# phy1.net
KiCad netlist of a schematic drawn in Altium Designer
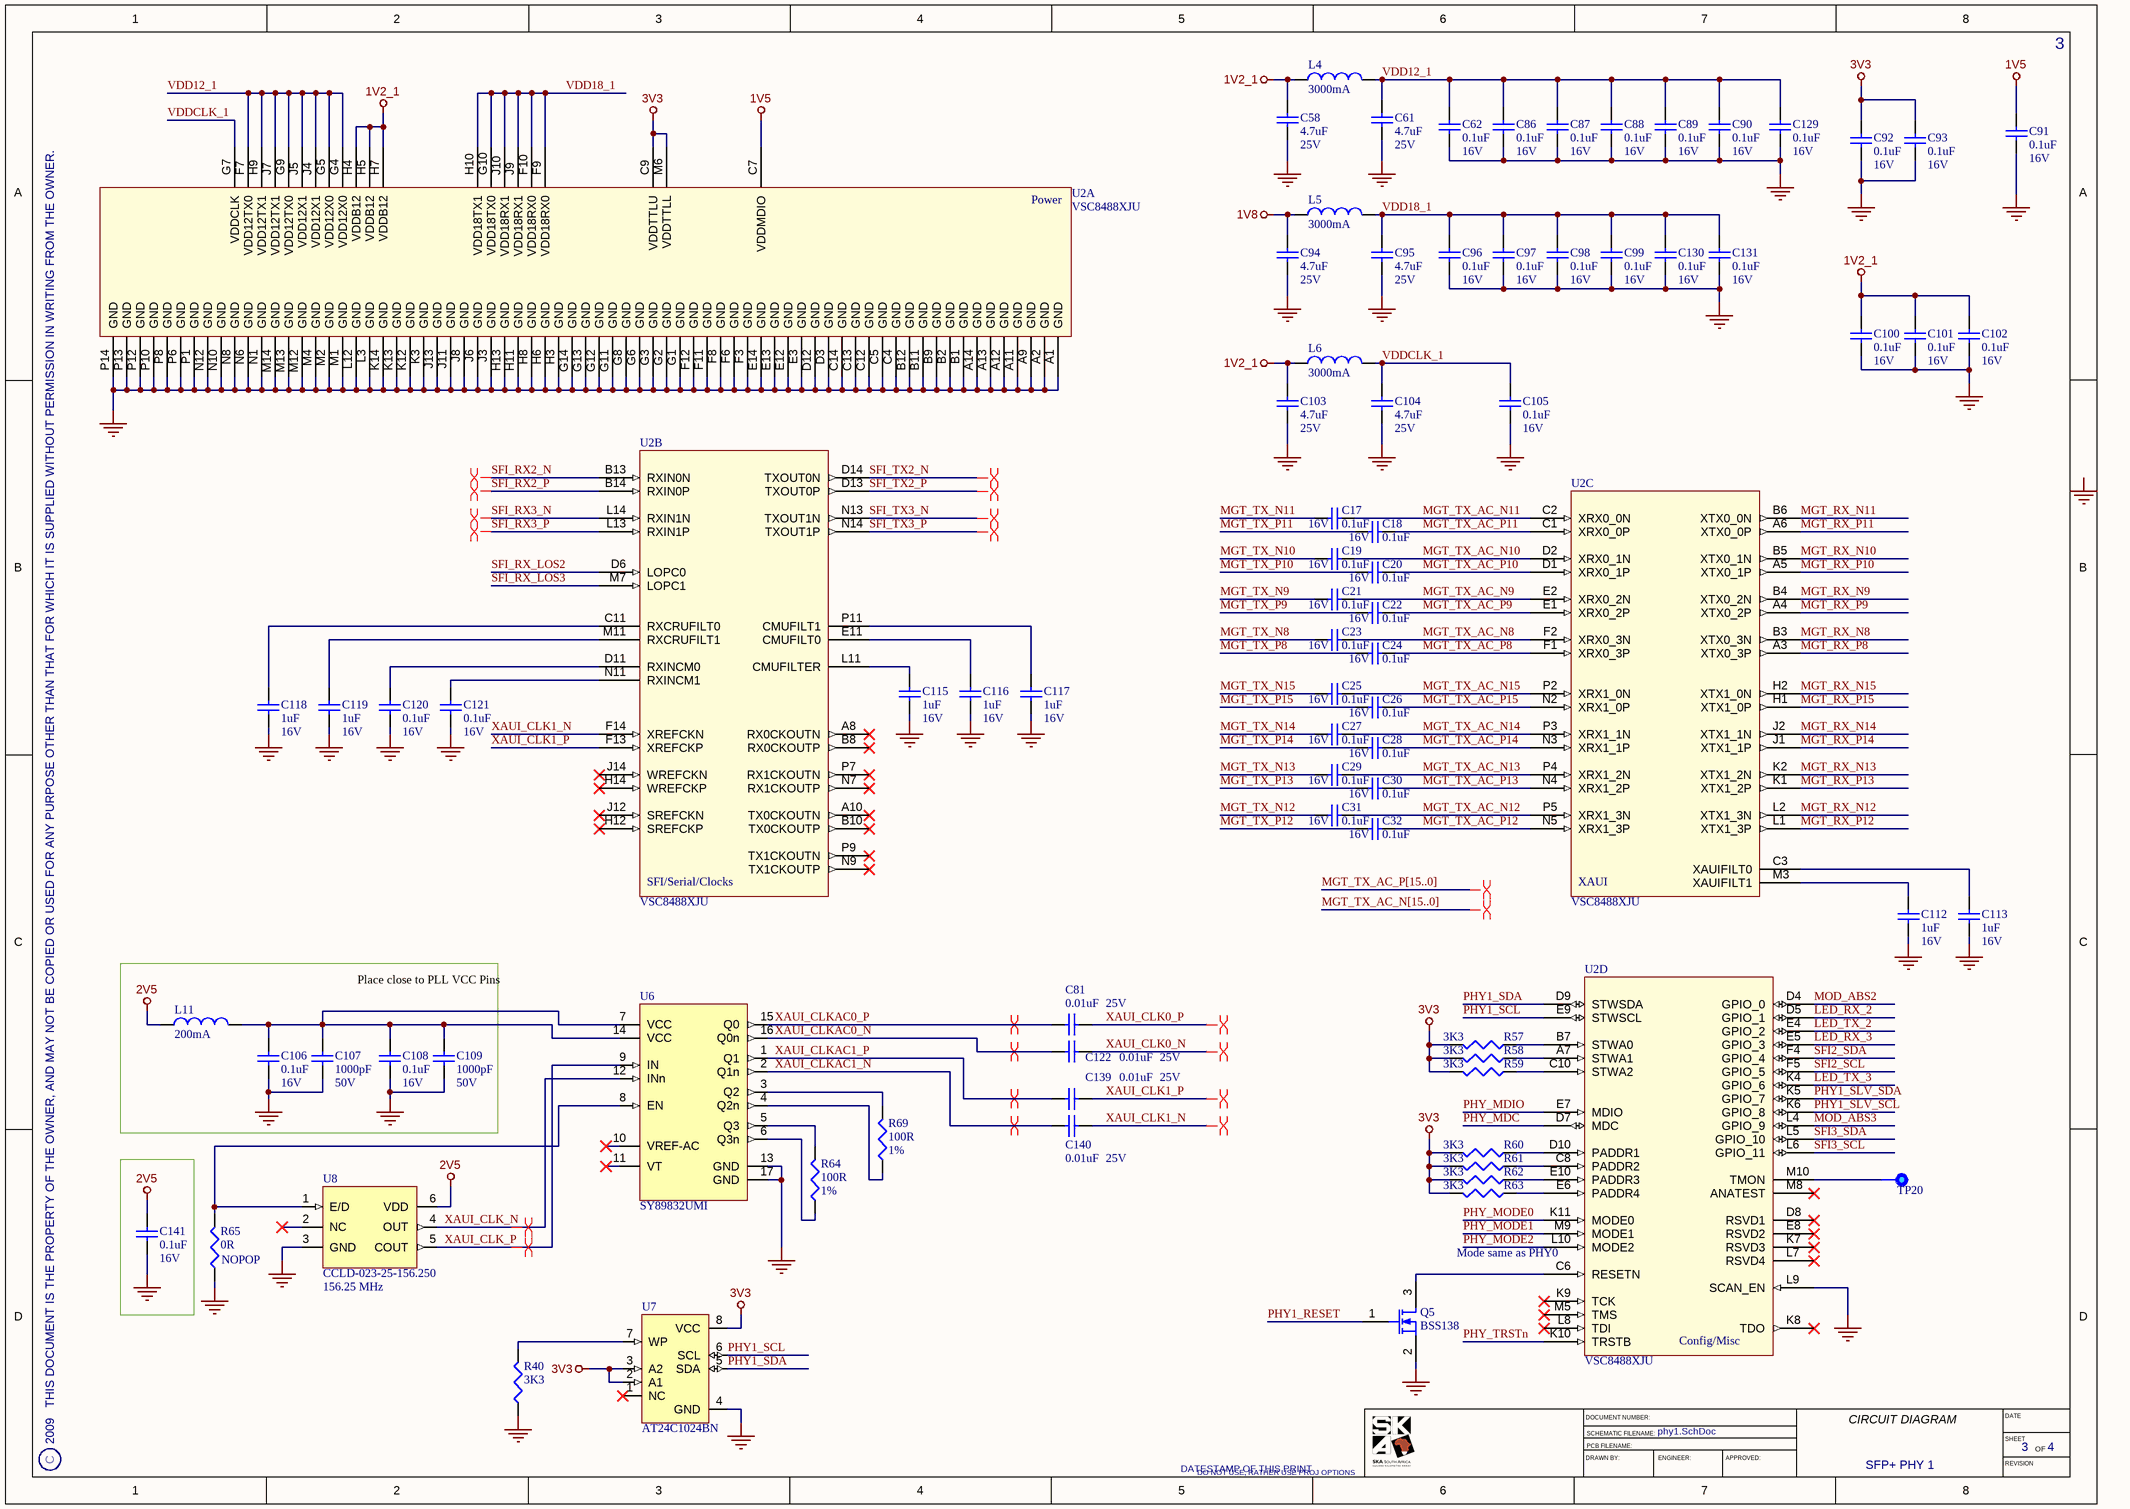
[diagram p0: phy1.SchDoc]

(export (version "E")
  (design (tool "Eeschema 10.0.6"))
  (components
    (comp (ref "C17")
      (value "0.1uF")
      (footprint "CAPC1005X60L")
      (description "0.1uF, Ceramic Capacitor")
      (fields
        (field (name "RATING") "16V")
        (field (name "MANUFACTURER") "VENKEL")
        (field (name "PARTNUM") "C0402X7R160-104KN")
      )
      (libsource (lib "altium_db") (part "CapStd"))
    )
    (comp (ref "C18")
      (value "0.1uF")
      (footprint "CAPC1005X60L")
      (description "0.1uF, Ceramic Capacitor")
      (fields
        (field (name "RATING") "16V")
        (field (name "MANUFACTURER") "VENKEL")
        (field (name "PARTNUM") "C0402X7R160-104KN")
      )
      (libsource (lib "altium_db") (part "CapStd"))
    )
    (comp (ref "C19")
      (value "0.1uF")
      (footprint "CAPC1005X60L")
      (description "0.1uF, Ceramic Capacitor")
      (fields
        (field (name "RATING") "16V")
        (field (name "MANUFACTURER") "VENKEL")
        (field (name "PARTNUM") "C0402X7R160-104KN")
      )
      (libsource (lib "altium_db") (part "CapStd"))
    )
    (comp (ref "C20")
      (value "0.1uF")
      (footprint "CAPC1005X60L")
      (description "0.1uF, Ceramic Capacitor")
      (fields
        (field (name "RATING") "16V")
        (field (name "MANUFACTURER") "VENKEL")
        (field (name "PARTNUM") "C0402X7R160-104KN")
      )
      (libsource (lib "altium_db") (part "CapStd"))
    )
    (comp (ref "C21")
      (value "0.1uF")
      (footprint "CAPC1005X60L")
      (description "0.1uF, Ceramic Capacitor")
      (fields
        (field (name "RATING") "16V")
        (field (name "MANUFACTURER") "VENKEL")
        (field (name "PARTNUM") "C0402X7R160-104KN")
      )
      (libsource (lib "altium_db") (part "CapStd"))
    )
    (comp (ref "C22")
      (value "0.1uF")
      (footprint "CAPC1005X60L")
      (description "0.1uF, Ceramic Capacitor")
      (fields
        (field (name "RATING") "16V")
        (field (name "MANUFACTURER") "VENKEL")
        (field (name "PARTNUM") "C0402X7R160-104KN")
      )
      (libsource (lib "altium_db") (part "CapStd"))
    )
    (comp (ref "C23")
      (value "0.1uF")
      (footprint "CAPC1005X60L")
      (description "0.1uF, Ceramic Capacitor")
      (fields
        (field (name "RATING") "16V")
        (field (name "MANUFACTURER") "VENKEL")
        (field (name "PARTNUM") "C0402X7R160-104KN")
      )
      (libsource (lib "altium_db") (part "CapStd"))
    )
    (comp (ref "C24")
      (value "0.1uF")
      (footprint "CAPC1005X60L")
      (description "0.1uF, Ceramic Capacitor")
      (fields
        (field (name "RATING") "16V")
        (field (name "MANUFACTURER") "VENKEL")
        (field (name "PARTNUM") "C0402X7R160-104KN")
      )
      (libsource (lib "altium_db") (part "CapStd"))
    )
    (comp (ref "C25")
      (value "0.1uF")
      (footprint "CAPC1005X60L")
      (description "0.1uF, Ceramic Capacitor")
      (fields
        (field (name "RATING") "16V")
        (field (name "MANUFACTURER") "VENKEL")
        (field (name "PARTNUM") "C0402X7R160-104KN")
      )
      (libsource (lib "altium_db") (part "CapStd"))
    )
    (comp (ref "C26")
      (value "0.1uF")
      (footprint "CAPC1005X60L")
      (description "0.1uF, Ceramic Capacitor")
      (fields
        (field (name "RATING") "16V")
        (field (name "MANUFACTURER") "VENKEL")
        (field (name "PARTNUM") "C0402X7R160-104KN")
      )
      (libsource (lib "altium_db") (part "CapStd"))
    )
    (comp (ref "C27")
      (value "0.1uF")
      (footprint "CAPC1005X60L")
      (description "0.1uF, Ceramic Capacitor")
      (fields
        (field (name "RATING") "16V")
        (field (name "MANUFACTURER") "VENKEL")
        (field (name "PARTNUM") "C0402X7R160-104KN")
      )
      (libsource (lib "altium_db") (part "CapStd"))
    )
    (comp (ref "C28")
      (value "0.1uF")
      (footprint "CAPC1005X60L")
      (description "0.1uF, Ceramic Capacitor")
      (fields
        (field (name "RATING") "16V")
        (field (name "MANUFACTURER") "VENKEL")
        (field (name "PARTNUM") "C0402X7R160-104KN")
      )
      (libsource (lib "altium_db") (part "CapStd"))
    )
    (comp (ref "C29")
      (value "0.1uF")
      (footprint "CAPC1005X60L")
      (description "0.1uF, Ceramic Capacitor")
      (fields
        (field (name "RATING") "16V")
        (field (name "MANUFACTURER") "VENKEL")
        (field (name "PARTNUM") "C0402X7R160-104KN")
      )
      (libsource (lib "altium_db") (part "CapStd"))
    )
    (comp (ref "C30")
      (value "0.1uF")
      (footprint "CAPC1005X60L")
      (description "0.1uF, Ceramic Capacitor")
      (fields
        (field (name "RATING") "16V")
        (field (name "MANUFACTURER") "VENKEL")
        (field (name "PARTNUM") "C0402X7R160-104KN")
      )
      (libsource (lib "altium_db") (part "CapStd"))
    )
    (comp (ref "C31")
      (value "0.1uF")
      (footprint "CAPC1005X60L")
      (description "0.1uF, Ceramic Capacitor")
      (fields
        (field (name "RATING") "16V")
        (field (name "MANUFACTURER") "VENKEL")
        (field (name "PARTNUM") "C0402X7R160-104KN")
      )
      (libsource (lib "altium_db") (part "CapStd"))
    )
    (comp (ref "C32")
      (value "0.1uF")
      (footprint "CAPC1005X60L")
      (description "0.1uF, Ceramic Capacitor")
      (fields
        (field (name "RATING") "16V")
        (field (name "MANUFACTURER") "VENKEL")
        (field (name "PARTNUM") "C0402X7R160-104KN")
      )
      (libsource (lib "altium_db") (part "CapStd"))
    )
    (comp (ref "C58")
      (value "4.7uF")
      (footprint "CAPC2012X127L")
      (description "4.7uF, Ceramic Capacitor")
      (fields
        (field (name "RATING") "25V")
        (field (name "MANUFACTURER") "MURATA")
        (field (name "PARTNUM") "GRM21BR61E475KA12K")
      )
      (libsource (lib "altium_db") (part "CapStd"))
    )
    (comp (ref "C61")
      (value "4.7uF")
      (footprint "CAPC2012X127L")
      (description "4.7uF, Ceramic Capacitor")
      (fields
        (field (name "RATING") "25V")
        (field (name "MANUFACTURER") "MURATA")
        (field (name "PARTNUM") "GRM21BR61E475KA12K")
      )
      (libsource (lib "altium_db") (part "CapStd"))
    )
    (comp (ref "C62")
      (value "0.1uF")
      (footprint "CAPC1005X60L")
      (description "0.1uF, Ceramic Capacitor")
      (fields
        (field (name "RATING") "16V")
        (field (name "MANUFACTURER") "VENKEL")
        (field (name "PARTNUM") "C0402X7R160-104KN")
      )
      (libsource (lib "altium_db") (part "CapStd"))
    )
    (comp (ref "C81")
      (value "0.01uF")
      (footprint "CAPC1005X55L")
      (description "0.01uF, Ceramic Capacitor")
      (fields
        (field (name "RATING") "25V")
        (field (name "MANUFACTURER") "MURATA")
        (field (name "PARTNUM") "GRM155R71E103KA01D")
      )
      (libsource (lib "altium_db") (part "CapStd"))
    )
    (comp (ref "C86")
      (value "0.1uF")
      (footprint "CAPC1005X60L")
      (description "0.1uF, Ceramic Capacitor")
      (fields
        (field (name "RATING") "16V")
        (field (name "MANUFACTURER") "VENKEL")
        (field (name "PARTNUM") "C0402X7R160-104KN")
      )
      (libsource (lib "altium_db") (part "CapStd"))
    )
    (comp (ref "C87")
      (value "0.1uF")
      (footprint "CAPC1005X60L")
      (description "0.1uF, Ceramic Capacitor")
      (fields
        (field (name "RATING") "16V")
        (field (name "MANUFACTURER") "VENKEL")
        (field (name "PARTNUM") "C0402X7R160-104KN")
      )
      (libsource (lib "altium_db") (part "CapStd"))
    )
    (comp (ref "C88")
      (value "0.1uF")
      (footprint "CAPC1005X60L")
      (description "0.1uF, Ceramic Capacitor")
      (fields
        (field (name "RATING") "16V")
        (field (name "MANUFACTURER") "VENKEL")
        (field (name "PARTNUM") "C0402X7R160-104KN")
      )
      (libsource (lib "altium_db") (part "CapStd"))
    )
    (comp (ref "C89")
      (value "0.1uF")
      (footprint "CAPC1005X60L")
      (description "0.1uF, Ceramic Capacitor")
      (fields
        (field (name "RATING") "16V")
        (field (name "MANUFACTURER") "VENKEL")
        (field (name "PARTNUM") "C0402X7R160-104KN")
      )
      (libsource (lib "altium_db") (part "CapStd"))
    )
    (comp (ref "C90")
      (value "0.1uF")
      (footprint "CAPC1005X60L")
      (description "0.1uF, Ceramic Capacitor")
      (fields
        (field (name "RATING") "16V")
        (field (name "MANUFACTURER") "VENKEL")
        (field (name "PARTNUM") "C0402X7R160-104KN")
      )
      (libsource (lib "altium_db") (part "CapStd"))
    )
    (comp (ref "C91")
      (value "0.1uF")
      (footprint "CAPC1005X60L")
      (description "0.1uF, Ceramic Capacitor")
      (fields
        (field (name "RATING") "16V")
        (field (name "MANUFACTURER") "VENKEL")
        (field (name "PARTNUM") "C0402X7R160-104KN")
      )
      (libsource (lib "altium_db") (part "CapStd"))
    )
    (comp (ref "C92")
      (value "0.1uF")
      (footprint "CAPC1005X60L")
      (description "0.1uF, Ceramic Capacitor")
      (fields
        (field (name "RATING") "16V")
        (field (name "MANUFACTURER") "VENKEL")
        (field (name "PARTNUM") "C0402X7R160-104KN")
      )
      (libsource (lib "altium_db") (part "CapStd"))
    )
    (comp (ref "C93")
      (value "0.1uF")
      (footprint "CAPC1005X60L")
      (description "0.1uF, Ceramic Capacitor")
      (fields
        (field (name "RATING") "16V")
        (field (name "MANUFACTURER") "VENKEL")
        (field (name "PARTNUM") "C0402X7R160-104KN")
      )
      (libsource (lib "altium_db") (part "CapStd"))
    )
    (comp (ref "C94")
      (value "4.7uF")
      (footprint "CAPC2012X127L")
      (description "4.7uF, Ceramic Capacitor")
      (fields
        (field (name "RATING") "25V")
        (field (name "MANUFACTURER") "MURATA")
        (field (name "PARTNUM") "GRM21BR61E475KA12K")
      )
      (libsource (lib "altium_db") (part "CapStd"))
    )
    (comp (ref "C95")
      (value "4.7uF")
      (footprint "CAPC2012X127L")
      (description "4.7uF, Ceramic Capacitor")
      (fields
        (field (name "RATING") "25V")
        (field (name "MANUFACTURER") "MURATA")
        (field (name "PARTNUM") "GRM21BR61E475KA12K")
      )
      (libsource (lib "altium_db") (part "CapStd"))
    )
    (comp (ref "C96")
      (value "0.1uF")
      (footprint "CAPC1005X60L")
      (description "0.1uF, Ceramic Capacitor")
      (fields
        (field (name "RATING") "16V")
        (field (name "MANUFACTURER") "VENKEL")
        (field (name "PARTNUM") "C0402X7R160-104KN")
      )
      (libsource (lib "altium_db") (part "CapStd"))
    )
    (comp (ref "C97")
      (value "0.1uF")
      (footprint "CAPC1005X60L")
      (description "0.1uF, Ceramic Capacitor")
      (fields
        (field (name "RATING") "16V")
        (field (name "MANUFACTURER") "VENKEL")
        (field (name "PARTNUM") "C0402X7R160-104KN")
      )
      (libsource (lib "altium_db") (part "CapStd"))
    )
    (comp (ref "C98")
      (value "0.1uF")
      (footprint "CAPC1005X60L")
      (description "0.1uF, Ceramic Capacitor")
      (fields
        (field (name "RATING") "16V")
        (field (name "MANUFACTURER") "VENKEL")
        (field (name "PARTNUM") "C0402X7R160-104KN")
      )
      (libsource (lib "altium_db") (part "CapStd"))
    )
    (comp (ref "C99")
      (value "0.1uF")
      (footprint "CAPC1005X60L")
      (description "0.1uF, Ceramic Capacitor")
      (fields
        (field (name "RATING") "16V")
        (field (name "MANUFACTURER") "VENKEL")
        (field (name "PARTNUM") "C0402X7R160-104KN")
      )
      (libsource (lib "altium_db") (part "CapStd"))
    )
    (comp (ref "C100")
      (value "0.1uF")
      (footprint "CAPC1005X60L")
      (description "0.1uF, Ceramic Capacitor")
      (fields
        (field (name "RATING") "16V")
        (field (name "MANUFACTURER") "VENKEL")
        (field (name "PARTNUM") "C0402X7R160-104KN")
      )
      (libsource (lib "altium_db") (part "CapStd"))
    )
    (comp (ref "C101")
      (value "0.1uF")
      (footprint "CAPC1005X60L")
      (description "0.1uF, Ceramic Capacitor")
      (fields
        (field (name "RATING") "16V")
        (field (name "MANUFACTURER") "VENKEL")
        (field (name "PARTNUM") "C0402X7R160-104KN")
      )
      (libsource (lib "altium_db") (part "CapStd"))
    )
    (comp (ref "C102")
      (value "0.1uF")
      (footprint "CAPC1005X60L")
      (description "0.1uF, Ceramic Capacitor")
      (fields
        (field (name "RATING") "16V")
        (field (name "MANUFACTURER") "VENKEL")
        (field (name "PARTNUM") "C0402X7R160-104KN")
      )
      (libsource (lib "altium_db") (part "CapStd"))
    )
    (comp (ref "C103")
      (value "4.7uF")
      (footprint "CAPC2012X127L")
      (description "4.7uF, Ceramic Capacitor")
      (fields
        (field (name "RATING") "25V")
        (field (name "MANUFACTURER") "MURATA")
        (field (name "PARTNUM") "GRM21BR61E475KA12K")
      )
      (libsource (lib "altium_db") (part "CapStd"))
    )
    (comp (ref "C104")
      (value "4.7uF")
      (footprint "CAPC2012X127L")
      (description "4.7uF, Ceramic Capacitor")
      (fields
        (field (name "RATING") "25V")
        (field (name "MANUFACTURER") "MURATA")
        (field (name "PARTNUM") "GRM21BR61E475KA12K")
      )
      (libsource (lib "altium_db") (part "CapStd"))
    )
    (comp (ref "C105")
      (value "0.1uF")
      (footprint "CAPC1005X60L")
      (description "0.1uF, Ceramic Capacitor")
      (fields
        (field (name "RATING") "16V")
        (field (name "MANUFACTURER") "VENKEL")
        (field (name "PARTNUM") "C0402X7R160-104KN")
      )
      (libsource (lib "altium_db") (part "CapStd"))
    )
    (comp (ref "C106")
      (value "0.1uF")
      (footprint "CAPC1005X60L")
      (description "0.1uF, Ceramic Capacitor")
      (fields
        (field (name "RATING") "16V")
        (field (name "MANUFACTURER") "VENKEL")
        (field (name "PARTNUM") "C0402X7R160-104KN")
      )
      (libsource (lib "altium_db") (part "CapStd"))
    )
    (comp (ref "C107")
      (value "1000pF")
      (footprint "CAPC1005X55L")
      (description "1000pF, Ceramic Capacitor")
      (fields
        (field (name "RATING") "50V")
        (field (name "MANUFACTURER") "MURATA")
        (field (name "PARTNUM") "GRM155R61H102KA01D")
      )
      (libsource (lib "altium_db") (part "CapStd"))
    )
    (comp (ref "C108")
      (value "0.1uF")
      (footprint "CAPC1005X60L")
      (description "0.1uF, Ceramic Capacitor")
      (fields
        (field (name "RATING") "16V")
        (field (name "MANUFACTURER") "VENKEL")
        (field (name "PARTNUM") "C0402X7R160-104KN")
      )
      (libsource (lib "altium_db") (part "CapStd"))
    )
    (comp (ref "C109")
      (value "1000pF")
      (footprint "CAPC1005X55L")
      (description "1000pF, Ceramic Capacitor")
      (fields
        (field (name "RATING") "50V")
        (field (name "MANUFACTURER") "MURATA")
        (field (name "PARTNUM") "GRM155R61H102KA01D")
      )
      (libsource (lib "altium_db") (part "CapStd"))
    )
    (comp (ref "C112")
      (value "1uF")
      (footprint "CAPC2012X127L")
      (description "1uF, Ceramic Capacitor")
      (fields
        (field (name "RATING") "16V")
        (field (name "MANUFACTURER") "MURATA")
        (field (name "PARTNUM") "GRM21BR61C105KA01L")
      )
      (libsource (lib "altium_db") (part "CapStd"))
    )
    (comp (ref "C113")
      (value "1uF")
      (footprint "CAPC2012X127L")
      (description "1uF, Ceramic Capacitor")
      (fields
        (field (name "RATING") "16V")
        (field (name "MANUFACTURER") "MURATA")
        (field (name "PARTNUM") "GRM21BR61C105KA01L")
      )
      (libsource (lib "altium_db") (part "CapStd"))
    )
    (comp (ref "C115")
      (value "1uF")
      (footprint "CAPC2012X127L")
      (description "1uF, Ceramic Capacitor")
      (fields
        (field (name "RATING") "16V")
        (field (name "MANUFACTURER") "MURATA")
        (field (name "PARTNUM") "GRM21BR61C105KA01L")
      )
      (libsource (lib "altium_db") (part "CapStd"))
    )
    (comp (ref "C116")
      (value "1uF")
      (footprint "CAPC2012X127L")
      (description "1uF, Ceramic Capacitor")
      (fields
        (field (name "RATING") "16V")
        (field (name "MANUFACTURER") "MURATA")
        (field (name "PARTNUM") "GRM21BR61C105KA01L")
      )
      (libsource (lib "altium_db") (part "CapStd"))
    )
    (comp (ref "C117")
      (value "1uF")
      (footprint "CAPC2012X127L")
      (description "1uF, Ceramic Capacitor")
      (fields
        (field (name "RATING") "16V")
        (field (name "MANUFACTURER") "MURATA")
        (field (name "PARTNUM") "GRM21BR61C105KA01L")
      )
      (libsource (lib "altium_db") (part "CapStd"))
    )
    (comp (ref "C118")
      (value "1uF")
      (footprint "CAPC2012X127L")
      (description "1uF, Ceramic Capacitor")
      (fields
        (field (name "RATING") "16V")
        (field (name "MANUFACTURER") "MURATA")
        (field (name "PARTNUM") "GRM21BR61C105KA01L")
      )
      (libsource (lib "altium_db") (part "CapStd"))
    )
    (comp (ref "C119")
      (value "1uF")
      (footprint "CAPC2012X127L")
      (description "1uF, Ceramic Capacitor")
      (fields
        (field (name "RATING") "16V")
        (field (name "MANUFACTURER") "MURATA")
        (field (name "PARTNUM") "GRM21BR61C105KA01L")
      )
      (libsource (lib "altium_db") (part "CapStd"))
    )
    (comp (ref "C120")
      (value "0.1uF")
      (footprint "CAPC1005X60L")
      (description "0.1uF, Ceramic Capacitor")
      (fields
        (field (name "RATING") "16V")
        (field (name "MANUFACTURER") "VENKEL")
        (field (name "PARTNUM") "C0402X7R160-104KN")
      )
      (libsource (lib "altium_db") (part "CapStd"))
    )
    (comp (ref "C121")
      (value "0.1uF")
      (footprint "CAPC1005X60L")
      (description "0.1uF, Ceramic Capacitor")
      (fields
        (field (name "RATING") "16V")
        (field (name "MANUFACTURER") "VENKEL")
        (field (name "PARTNUM") "C0402X7R160-104KN")
      )
      (libsource (lib "altium_db") (part "CapStd"))
    )
    (comp (ref "C122")
      (value "0.01uF")
      (footprint "CAPC1005X55L")
      (description "0.01uF, Ceramic Capacitor")
      (fields
        (field (name "RATING") "25V")
        (field (name "MANUFACTURER") "MURATA")
        (field (name "PARTNUM") "GRM155R71E103KA01D")
      )
      (libsource (lib "altium_db") (part "CapStd"))
    )
    (comp (ref "C129")
      (value "0.1uF")
      (footprint "CAPC1005X60L")
      (description "0.1uF, Ceramic Capacitor")
      (fields
        (field (name "RATING") "16V")
        (field (name "MANUFACTURER") "VENKEL")
        (field (name "PARTNUM") "C0402X7R160-104KN")
      )
      (libsource (lib "altium_db") (part "CapStd"))
    )
    (comp (ref "C130")
      (value "0.1uF")
      (footprint "CAPC1005X60L")
      (description "0.1uF, Ceramic Capacitor")
      (fields
        (field (name "RATING") "16V")
        (field (name "MANUFACTURER") "VENKEL")
        (field (name "PARTNUM") "C0402X7R160-104KN")
      )
      (libsource (lib "altium_db") (part "CapStd"))
    )
    (comp (ref "C131")
      (value "0.1uF")
      (footprint "CAPC1005X60L")
      (description "0.1uF, Ceramic Capacitor")
      (fields
        (field (name "RATING") "16V")
        (field (name "MANUFACTURER") "VENKEL")
        (field (name "PARTNUM") "C0402X7R160-104KN")
      )
      (libsource (lib "altium_db") (part "CapStd"))
    )
    (comp (ref "C139")
      (value "0.01uF")
      (footprint "CAPC1005X55L")
      (description "0.01uF, Ceramic Capacitor")
      (fields
        (field (name "RATING") "25V")
        (field (name "MANUFACTURER") "MURATA")
        (field (name "PARTNUM") "GRM155R71E103KA01D")
      )
      (libsource (lib "altium_db") (part "CapStd"))
    )
    (comp (ref "C140")
      (value "0.01uF")
      (footprint "CAPC1005X55L")
      (description "0.01uF, Ceramic Capacitor")
      (fields
        (field (name "RATING") "25V")
        (field (name "MANUFACTURER") "MURATA")
        (field (name "PARTNUM") "GRM155R71E103KA01D")
      )
      (libsource (lib "altium_db") (part "CapStd"))
    )
    (comp (ref "C141")
      (value "0.1uF")
      (footprint "CAPC1005X60L")
      (description "0.1uF, Ceramic Capacitor")
      (fields
        (field (name "RATING") "16V")
        (field (name "MANUFACTURER") "VENKEL")
        (field (name "PARTNUM") "C0402X7R160-104KN")
      )
      (libsource (lib "altium_db") (part "CapStd"))
    )
    (comp (ref "L4")
      (value "120R")
      (footprint "INDC3216X130L")
      (description "120 Ohm, Chip Ferrite Brad")
      (fields
        (field (name "RATING") "3000mA")
        (field (name "MANUFACTURER") "Murata")
        (field (name "PARTNUM") "BLM31PG121SN1")
      )
      (libsource (lib "altium_db") (part "IndStd"))
    )
    (comp (ref "L5")
      (value "120R")
      (footprint "INDC3216X130L")
      (description "120 Ohm, Chip Ferrite Brad")
      (fields
        (field (name "RATING") "3000mA")
        (field (name "MANUFACTURER") "Murata")
        (field (name "PARTNUM") "BLM31PG121SN1")
      )
      (libsource (lib "altium_db") (part "IndStd"))
    )
    (comp (ref "L6")
      (value "120R")
      (footprint "INDC3216X130L")
      (description "120 Ohm, Chip Ferrite Brad")
      (fields
        (field (name "RATING") "3000mA")
        (field (name "MANUFACTURER") "Murata")
        (field (name "PARTNUM") "BLM31PG121SN1")
      )
      (libsource (lib "altium_db") (part "IndStd"))
    )
    (comp (ref "L11")
      (value "600R")
      (footprint "INDC2012X130L")
      (description "600 Ohm, Chip Ferrite Bead")
      (fields
        (field (name "RATING") "200mA")
        (field (name "MANUFACTURER") "Murata")
        (field (name "PARTNUM") "BLM21BD601SN1")
      )
      (libsource (lib "altium_db") (part "IndStd"))
    )
    (comp (ref "Q5")
      (value "BSS138")
      (footprint "SOT95P245X110-3N")
      (description "N-Channel Logic Level Enhancement Mode Field Effect Transistor")
      (fields (field (name "MANUFACTURER") "Fairchild Semiconductor"))
      (libsource (lib "altium_db") (part "BSS138"))
    )
    (comp (ref "R40")
      (value "3K3")
      (footprint "RESC1005X40L")
      (description "3K3, 1.1mm x 0.5mm, Thick Film Resistor")
      (fields (field (name "MANUFACTURER") "ROYALOHM") (field (name "PARTNUM") "0402WGJ0332T1E"))
      (libsource (lib "altium_db") (part "ResStd"))
    )
    (comp (ref "R57")
      (value "3K3")
      (footprint "RESC1005X40L")
      (description "3K3, 1.1mm x 0.5mm, Thick Film Resistor")
      (fields (field (name "MANUFACTURER") "ROYALOHM") (field (name "PARTNUM") "0402WGJ0332T1E"))
      (libsource (lib "altium_db") (part "ResStd"))
    )
    (comp (ref "R58")
      (value "3K3")
      (footprint "RESC1005X40L")
      (description "3K3, 1.1mm x 0.5mm, Thick Film Resistor")
      (fields (field (name "MANUFACTURER") "ROYALOHM") (field (name "PARTNUM") "0402WGJ0332T1E"))
      (libsource (lib "altium_db") (part "ResStd"))
    )
    (comp (ref "R59")
      (value "3K3")
      (footprint "RESC1005X40L")
      (description "3K3, 1.1mm x 0.5mm, Thick Film Resistor")
      (fields (field (name "MANUFACTURER") "ROYALOHM") (field (name "PARTNUM") "0402WGJ0332T1E"))
      (libsource (lib "altium_db") (part "ResStd"))
    )
    (comp (ref "R60")
      (value "3K3")
      (footprint "RESC1005X40L")
      (description "3K3, 1.1mm x 0.5mm, Thick Film Resistor")
      (fields (field (name "MANUFACTURER") "ROYALOHM") (field (name "PARTNUM") "0402WGJ0332T1E"))
      (libsource (lib "altium_db") (part "ResStd"))
    )
    (comp (ref "R61")
      (value "3K3")
      (footprint "RESC1005X40L")
      (description "3K3, 1.1mm x 0.5mm, Thick Film Resistor")
      (fields (field (name "MANUFACTURER") "ROYALOHM") (field (name "PARTNUM") "0402WGJ0332T1E"))
      (libsource (lib "altium_db") (part "ResStd"))
    )
    (comp (ref "R62")
      (value "3K3")
      (footprint "RESC1005X40L")
      (description "3K3, 1.1mm x 0.5mm, Thick Film Resistor")
      (fields (field (name "MANUFACTURER") "ROYALOHM") (field (name "PARTNUM") "0402WGJ0332T1E"))
      (libsource (lib "altium_db") (part "ResStd"))
    )
    (comp (ref "R63")
      (value "3K3")
      (footprint "RESC1005X40L")
      (description "3K3, 1.1mm x 0.5mm, Thick Film Resistor")
      (fields (field (name "MANUFACTURER") "ROYALOHM") (field (name "PARTNUM") "0402WGJ0332T1E"))
      (libsource (lib "altium_db") (part "ResStd"))
    )
    (comp (ref "R64")
      (value "100R")
      (footprint "RESC1005X40L")
      (description "100R, 1.1mm x 0.5mm, Thick Film Resistor")
      (fields
        (field (name "MANUFACTURER") "ROYALOHM")
        (field (name "PARTNUM") "0402WGF0101T1E")
        (field (name "TOLERANCE") "1%")
      )
      (libsource (lib "altium_db") (part "ResStd"))
    )
    (comp (ref "R65")
      (value "0R")
      (footprint "RESC1005X40L")
      (description "0R, 1.1mm x 0.5mm, Thick Film Resistor")
      (fields (field (name "MANUFACTURER") "ROYALOHM") (field (name "PARTNUM") "0402WG00000T1E"))
      (libsource (lib "altium_db") (part "ResStd"))
    )
    (comp (ref "R69")
      (value "100R")
      (footprint "RESC1005X40L")
      (description "100R, 1.1mm x 0.5mm, Thick Film Resistor")
      (fields
        (field (name "MANUFACTURER") "ROYALOHM")
        (field (name "PARTNUM") "0402WGF0101T1E")
        (field (name "TOLERANCE") "1%")
      )
      (libsource (lib "altium_db") (part "ResStd"))
    )
    (comp (ref "TP20")
      (value "Testpoint")
      (footprint "TP100")
      (description "1mm Diameter, through-hole, Circular Test-point")
      (libsource (lib "altium_db") (part "Testpoint"))
    )
    (comp (ref "U2")
      (value "VSC8488XJU")
      (footprint "BGA196C100P14X14_1500x1500x140")
      (description "DualChannel WAN/LAN/Backplane XAUI to SFP+/KR Transceiver")
      (fields (field (name "MANUFACTURER") "Vitesse"))
      (libsource (lib "altium_db") (part "VSC8488XJU"))
    )
    (comp (ref "U6")
      (value "SY89832UMI")
      (footprint "MLF-16")
      (description "2.5 C Ultra-precision 1:4 LVDS Fanout Buffer/Translator with Interal Termination")
      (fields (field (name "MANUFACTURER") "Micrel"))
      (libsource (lib "altium_db") (part "SY89832UMI"))
    )
    (comp (ref "U7")
      (value "AT24C1024BN")
      (footprint "SOIC150-8_N")
      (description "1M, SOIC-8, Serial EEPROM")
      (fields (field (name "MANUFACTURER") "Atmel") (field (name "PARTNUM") "AT24C1024BN-SH-B"))
      (libsource (lib "altium_db") (part "AT24C1024BN-SH"))
    )
    (comp (ref "U8")
      (value "CCLD-023-25-156.250")
      (footprint "CCLD-023X-XX-XXX_XXX")
      (description "156.25 MHz, Low-Jitter Differential LVDS Clock Oscillator")
      (fields
        (field (name "PARTNUM") "CCLD-023-25-156.250")
        (field (name "FREQUENCY") "156.25 MHz")
        (field (name "MANUFACTURER") "Crystek")
      )
      (libsource (lib "altium_db") (part "CCLD-023X-XX-XXX_XXX"))
    )
  )
  (nets
    (net (code "17") (name "/LED_RX_2") (class "Default")
      (node (ref "U2") (pin "D5") (pinfunction "GPIO_1_D5") (pintype "bidirectional"))
    )
    (net (code "18") (name "/LED_RX_3") (class "Default")
      (node (ref "U2") (pin "E5") (pinfunction "GPIO_3_E5") (pintype "bidirectional"))
    )
    (net (code "19") (name "/LED_TX_2") (class "Default")
      (node (ref "U2") (pin "E4") (pinfunction "GPIO_2_E4") (pintype "bidirectional"))
    )
    (net (code "20") (name "/LED_TX_3") (class "Default")
      (node (ref "U2") (pin "K4") (pinfunction "GPIO_6_K4") (pintype "bidirectional"))
    )
    (net (code "21") (name "/MGT_RX_N8") (class "Default")
      (node (ref "U2") (pin "B3") (pinfunction "XTX0_3N_B3") (pintype "output"))
    )
    (net (code "22") (name "/MGT_RX_N9") (class "Default")
      (node (ref "U2") (pin "B4") (pinfunction "XTX0_2N_B4") (pintype "output"))
    )
    (net (code "23") (name "/MGT_RX_N10") (class "Default")
      (node (ref "U2") (pin "B5") (pinfunction "XTX0_1N_B5") (pintype "output"))
    )
    (net (code "24") (name "/MGT_RX_N11") (class "Default")
      (node (ref "U2") (pin "B6") (pinfunction "XTX0_0N_B6") (pintype "output"))
    )
    (net (code "25") (name "/MGT_RX_N12") (class "Default")
      (node (ref "U2") (pin "L2") (pinfunction "XTX1_3N_L2") (pintype "output"))
    )
    (net (code "26") (name "/MGT_RX_N13") (class "Default")
      (node (ref "U2") (pin "K2") (pinfunction "XTX1_2N_K2") (pintype "output"))
    )
    (net (code "27") (name "/MGT_RX_N14") (class "Default")
      (node (ref "U2") (pin "J2") (pinfunction "XTX1_1N_J2") (pintype "output"))
    )
    (net (code "28") (name "/MGT_RX_N15") (class "Default")
      (node (ref "U2") (pin "H2") (pinfunction "XTX1_0N_H2") (pintype "output"))
    )
    (net (code "29") (name "/MGT_RX_P8") (class "Default")
      (node (ref "U2") (pin "A3") (pinfunction "XTX0_3P_A3") (pintype "output"))
    )
    (net (code "30") (name "/MGT_RX_P9") (class "Default")
      (node (ref "U2") (pin "A4") (pinfunction "XTX0_2P_A4") (pintype "output"))
    )
    (net (code "31") (name "/MGT_RX_P10") (class "Default")
      (node (ref "U2") (pin "A5") (pinfunction "XTX0_1P_A5") (pintype "output"))
    )
    (net (code "32") (name "/MGT_RX_P11") (class "Default")
      (node (ref "U2") (pin "A6") (pinfunction "XTX0_0P_A6") (pintype "output"))
    )
    (net (code "33") (name "/MGT_RX_P12") (class "Default")
      (node (ref "U2") (pin "L1") (pinfunction "XTX1_3P_L1") (pintype "output"))
    )
    (net (code "34") (name "/MGT_RX_P13") (class "Default")
      (node (ref "U2") (pin "K1") (pinfunction "XTX1_2P_K1") (pintype "output"))
    )
    (net (code "35") (name "/MGT_RX_P14") (class "Default")
      (node (ref "U2") (pin "J1") (pinfunction "XTX1_1P_J1") (pintype "output"))
    )
    (net (code "36") (name "/MGT_RX_P15") (class "Default")
      (node (ref "U2") (pin "H1") (pinfunction "XTX1_0P_H1") (pintype "output"))
    )
    (net (code "37") (name "/MGT_TX_AC_N8") (class "Default")
      (node (ref "C23") (pin "1") (pinfunction "1_1") (pintype "passive"))
      (node (ref "U2") (pin "F2") (pinfunction "XRX0_3N_F2") (pintype "input"))
    )
    (net (code "38") (name "/MGT_TX_AC_N9") (class "Default")
      (node (ref "C21") (pin "1") (pinfunction "1_1") (pintype "passive"))
      (node (ref "U2") (pin "E2") (pinfunction "XRX0_2N_E2") (pintype "input"))
    )
    (net (code "39") (name "/MGT_TX_AC_N10") (class "Default")
      (node (ref "C19") (pin "1") (pinfunction "1_1") (pintype "passive"))
      (node (ref "U2") (pin "D2") (pinfunction "XRX0_1N_D2") (pintype "input"))
    )
    (net (code "40") (name "/MGT_TX_AC_N11") (class "Default")
      (node (ref "C17") (pin "1") (pinfunction "1_1") (pintype "passive"))
      (node (ref "U2") (pin "C2") (pinfunction "XRX0_0N_C2") (pintype "input"))
    )
    (net (code "41") (name "/MGT_TX_AC_N12") (class "Default")
      (node (ref "C31") (pin "1") (pinfunction "1_1") (pintype "passive"))
      (node (ref "U2") (pin "P5") (pinfunction "XRX1_3N_P5") (pintype "input"))
    )
    (net (code "42") (name "/MGT_TX_AC_N13") (class "Default")
      (node (ref "C29") (pin "1") (pinfunction "1_1") (pintype "passive"))
      (node (ref "U2") (pin "P4") (pinfunction "XRX1_2N_P4") (pintype "input"))
    )
    (net (code "43") (name "/MGT_TX_AC_N14") (class "Default")
      (node (ref "C27") (pin "1") (pinfunction "1_1") (pintype "passive"))
      (node (ref "U2") (pin "P3") (pinfunction "XRX1_1N_P3") (pintype "input"))
    )
    (net (code "44") (name "/MGT_TX_AC_N15") (class "Default")
      (node (ref "C25") (pin "1") (pinfunction "1_1") (pintype "passive"))
      (node (ref "U2") (pin "P2") (pinfunction "XRX1_0N_P2") (pintype "input"))
    )
    (net (code "46") (name "/MGT_TX_AC_P8") (class "Default")
      (node (ref "C24") (pin "1") (pinfunction "1_1") (pintype "passive"))
      (node (ref "U2") (pin "F1") (pinfunction "XRX0_3P_F1") (pintype "input"))
    )
    (net (code "47") (name "/MGT_TX_AC_P9") (class "Default")
      (node (ref "C22") (pin "1") (pinfunction "1_1") (pintype "passive"))
      (node (ref "U2") (pin "E1") (pinfunction "XRX0_2P_E1") (pintype "input"))
    )
    (net (code "48") (name "/MGT_TX_AC_P10") (class "Default")
      (node (ref "C20") (pin "1") (pinfunction "1_1") (pintype "passive"))
      (node (ref "U2") (pin "D1") (pinfunction "XRX0_1P_D1") (pintype "input"))
    )
    (net (code "49") (name "/MGT_TX_AC_P11") (class "Default")
      (node (ref "C18") (pin "1") (pinfunction "1_1") (pintype "passive"))
      (node (ref "U2") (pin "C1") (pinfunction "XRX0_0P_C1") (pintype "input"))
    )
    (net (code "50") (name "/MGT_TX_AC_P12") (class "Default")
      (node (ref "C32") (pin "1") (pinfunction "1_1") (pintype "passive"))
      (node (ref "U2") (pin "N5") (pinfunction "XRX1_3P_N5") (pintype "input"))
    )
    (net (code "51") (name "/MGT_TX_AC_P13") (class "Default")
      (node (ref "C30") (pin "1") (pinfunction "1_1") (pintype "passive"))
      (node (ref "U2") (pin "N4") (pinfunction "XRX1_2P_N4") (pintype "input"))
    )
    (net (code "52") (name "/MGT_TX_AC_P14") (class "Default")
      (node (ref "C28") (pin "1") (pinfunction "1_1") (pintype "passive"))
      (node (ref "U2") (pin "N3") (pinfunction "XRX1_1P_N3") (pintype "input"))
    )
    (net (code "53") (name "/MGT_TX_AC_P15") (class "Default")
      (node (ref "C26") (pin "1") (pinfunction "1_1") (pintype "passive"))
      (node (ref "U2") (pin "N2") (pinfunction "XRX1_0P_N2") (pintype "input"))
    )
    (net (code "55") (name "/MGT_TX_N8") (class "Default")
      (node (ref "C23") (pin "2") (pinfunction "2_2") (pintype "passive"))
    )
    (net (code "56") (name "/MGT_TX_N9") (class "Default")
      (node (ref "C21") (pin "2") (pinfunction "2_2") (pintype "passive"))
    )
    (net (code "57") (name "/MGT_TX_N10") (class "Default")
      (node (ref "C19") (pin "2") (pinfunction "2_2") (pintype "passive"))
    )
    (net (code "58") (name "/MGT_TX_N11") (class "Default")
      (node (ref "C17") (pin "2") (pinfunction "2_2") (pintype "passive"))
    )
    (net (code "59") (name "/MGT_TX_N12") (class "Default")
      (node (ref "C31") (pin "2") (pinfunction "2_2") (pintype "passive"))
    )
    (net (code "60") (name "/MGT_TX_N13") (class "Default")
      (node (ref "C29") (pin "2") (pinfunction "2_2") (pintype "passive"))
    )
    (net (code "61") (name "/MGT_TX_N14") (class "Default")
      (node (ref "C27") (pin "2") (pinfunction "2_2") (pintype "passive"))
    )
    (net (code "62") (name "/MGT_TX_N15") (class "Default")
      (node (ref "C25") (pin "2") (pinfunction "2_2") (pintype "passive"))
    )
    (net (code "63") (name "/MGT_TX_P8") (class "Default")
      (node (ref "C24") (pin "2") (pinfunction "2_2") (pintype "passive"))
    )
    (net (code "64") (name "/MGT_TX_P9") (class "Default")
      (node (ref "C22") (pin "2") (pinfunction "2_2") (pintype "passive"))
    )
    (net (code "65") (name "/MGT_TX_P10") (class "Default")
      (node (ref "C20") (pin "2") (pinfunction "2_2") (pintype "passive"))
    )
    (net (code "66") (name "/MGT_TX_P11") (class "Default")
      (node (ref "C18") (pin "2") (pinfunction "2_2") (pintype "passive"))
    )
    (net (code "67") (name "/MGT_TX_P12") (class "Default")
      (node (ref "C32") (pin "2") (pinfunction "2_2") (pintype "passive"))
    )
    (net (code "68") (name "/MGT_TX_P13") (class "Default")
      (node (ref "C30") (pin "2") (pinfunction "2_2") (pintype "passive"))
    )
    (net (code "69") (name "/MGT_TX_P14") (class "Default")
      (node (ref "C28") (pin "2") (pinfunction "2_2") (pintype "passive"))
    )
    (net (code "70") (name "/MGT_TX_P15") (class "Default")
      (node (ref "C26") (pin "2") (pinfunction "2_2") (pintype "passive"))
    )
    (net (code "71") (name "/MOD_ABS2") (class "Default")
      (node (ref "U2") (pin "D4") (pinfunction "GPIO_0_D4") (pintype "bidirectional"))
    )
    (net (code "72") (name "/MOD_ABS3") (class "Default")
      (node (ref "U2") (pin "L4") (pinfunction "GPIO_9_L4") (pintype "bidirectional"))
    )
    (net (code "73") (name "/PHY1_RESET") (class "Default")
      (node (ref "Q5") (pin "1") (pinfunction "G_1") (pintype "passive"))
    )
    (net (code "74") (name "/PHY1_SCL") (class "Default")
      (node (ref "U2") (pin "E9") (pinfunction "STWSCL_E9") (pintype "bidirectional"))
      (node (ref "U7") (pin "6") (pinfunction "SCL_6") (pintype "bidirectional"))
    )
    (net (code "75") (name "/PHY1_SDA") (class "Default")
      (node (ref "U2") (pin "D9") (pinfunction "STWSDA_D9") (pintype "bidirectional"))
      (node (ref "U7") (pin "5") (pinfunction "SDA_5") (pintype "bidirectional"))
    )
    (net (code "76") (name "/PHY1_SLV_SCL") (class "Default")
      (node (ref "U2") (pin "K6") (pinfunction "GPIO_8_K6") (pintype "bidirectional"))
    )
    (net (code "77") (name "/PHY1_SLV_SDA") (class "Default")
      (node (ref "U2") (pin "K5") (pinfunction "GPIO_7_K5") (pintype "bidirectional"))
    )
    (net (code "78") (name "/PHY_MDC") (class "Default")
      (node (ref "U2") (pin "D7") (pinfunction "MDC_D7") (pintype "bidirectional"))
    )
    (net (code "79") (name "/PHY_MDIO") (class "Default")
      (node (ref "U2") (pin "E7") (pinfunction "MDIO_E7") (pintype "input"))
    )
    (net (code "80") (name "/PHY_MODE0") (class "Default")
      (node (ref "U2") (pin "K11") (pinfunction "MODE0_K11") (pintype "input"))
    )
    (net (code "81") (name "/PHY_MODE1") (class "Default")
      (node (ref "U2") (pin "M9") (pinfunction "MODE1_M9") (pintype "input"))
    )
    (net (code "82") (name "/PHY_MODE2") (class "Default")
      (node (ref "U2") (pin "L10") (pinfunction "MODE2_L10") (pintype "input"))
    )
    (net (code "83") (name "/PHY_TRSTn") (class "Default")
      (node (ref "U2") (pin "K10") (pinfunction "TRSTB_K10") (pintype "input"))
    )
    (net (code "84") (name "/SFI2_SCL") (class "Default")
      (node (ref "U2") (pin "F5") (pinfunction "GPIO_5_F5") (pintype "bidirectional"))
    )
    (net (code "85") (name "/SFI2_SDA") (class "Default")
      (node (ref "U2") (pin "F4") (pinfunction "GPIO_4_F4") (pintype "bidirectional"))
    )
    (net (code "86") (name "/SFI3_SCL") (class "Default")
      (node (ref "U2") (pin "L6") (pinfunction "GPIO_11_L6") (pintype "bidirectional"))
    )
    (net (code "87") (name "/SFI3_SDA") (class "Default")
      (node (ref "U2") (pin "L5") (pinfunction "GPIO_10_L5") (pintype "bidirectional"))
    )
    (net (code "88") (name "/SFI_RX2_N") (class "Default")
      (node (ref "U2") (pin "B13") (pinfunction "RXIN0N_B13") (pintype "input"))
    )
    (net (code "89") (name "/SFI_RX2_P") (class "Default")
      (node (ref "U2") (pin "B14") (pinfunction "RXIN0P_B14") (pintype "input"))
    )
    (net (code "90") (name "/SFI_RX3_N") (class "Default")
      (node (ref "U2") (pin "L14") (pinfunction "RXIN1N_L14") (pintype "input"))
    )
    (net (code "91") (name "/SFI_RX3_P") (class "Default")
      (node (ref "U2") (pin "L13") (pinfunction "RXIN1P_L13") (pintype "input"))
    )
    (net (code "92") (name "/SFI_RX_LOS2") (class "Default")
      (node (ref "U2") (pin "D6") (pinfunction "LOPC0_D6") (pintype "input"))
    )
    (net (code "93") (name "/SFI_RX_LOS3") (class "Default")
      (node (ref "U2") (pin "M7") (pinfunction "LOPC1_M7") (pintype "input"))
    )
    (net (code "94") (name "/SFI_TX2_N") (class "Default")
      (node (ref "U2") (pin "D14") (pinfunction "TXOUT0N_D14") (pintype "output"))
    )
    (net (code "95") (name "/SFI_TX2_P") (class "Default")
      (node (ref "U2") (pin "D13") (pinfunction "TXOUT0P_D13") (pintype "output"))
    )
    (net (code "96") (name "/SFI_TX3_N") (class "Default")
      (node (ref "U2") (pin "N13") (pinfunction "TXOUT1N_N13") (pintype "output"))
    )
    (net (code "97") (name "/SFI_TX3_P") (class "Default")
      (node (ref "U2") (pin "N14") (pinfunction "TXOUT1P_N14") (pintype "output"))
    )
    (net (code "98") (name "/VDD12_1") (class "Default")
      (node (ref "C129") (pin "2") (pinfunction "2_2") (pintype "passive"))
      (node (ref "C61") (pin "2") (pinfunction "2_2") (pintype "passive"))
      (node (ref "C62") (pin "2") (pinfunction "2_2") (pintype "passive"))
      (node (ref "C86") (pin "2") (pinfunction "2_2") (pintype "passive"))
      (node (ref "C87") (pin "2") (pinfunction "2_2") (pintype "passive"))
      (node (ref "C88") (pin "2") (pinfunction "2_2") (pintype "passive"))
      (node (ref "C89") (pin "2") (pinfunction "2_2") (pintype "passive"))
      (node (ref "C90") (pin "2") (pinfunction "2_2") (pintype "passive"))
      (node (ref "L4") (pin "2") (pinfunction "2_2") (pintype "passive"))
      (node (ref "U2") (pin "F7") (pinfunction "VDD12TX0_F7") (pintype "power_in"))
      (node (ref "U2") (pin "G4") (pinfunction "VDD12X0_G4") (pintype "power_in"))
      (node (ref "U2") (pin "G5") (pinfunction "VDD12X0_G5") (pintype "power_in"))
      (node (ref "U2") (pin "G9") (pinfunction "VDD12TX0_G9") (pintype "power_in"))
      (node (ref "U2") (pin "H9") (pinfunction "VDD12TX1_H9") (pintype "power_in"))
      (node (ref "U2") (pin "J4") (pinfunction "VDD12X1_J4") (pintype "power_in"))
      (node (ref "U2") (pin "J5") (pinfunction "VDD12X1_J5") (pintype "power_in"))
      (node (ref "U2") (pin "J7") (pinfunction "VDD12TX1_J7") (pintype "power_in"))
    )
    (net (code "99") (name "/VDD18_1") (class "Default")
      (node (ref "C130") (pin "2") (pinfunction "2_2") (pintype "passive"))
      (node (ref "C131") (pin "2") (pinfunction "2_2") (pintype "passive"))
      (node (ref "C95") (pin "2") (pinfunction "2_2") (pintype "passive"))
      (node (ref "C96") (pin "2") (pinfunction "2_2") (pintype "passive"))
      (node (ref "C97") (pin "2") (pinfunction "2_2") (pintype "passive"))
      (node (ref "C98") (pin "2") (pinfunction "2_2") (pintype "passive"))
      (node (ref "C99") (pin "2") (pinfunction "2_2") (pintype "passive"))
      (node (ref "L5") (pin "2") (pinfunction "2_2") (pintype "passive"))
      (node (ref "U2") (pin "F10") (pinfunction "VDD18RX0_F10") (pintype "power_in"))
      (node (ref "U2") (pin "F9") (pinfunction "VDD18RX0_F9") (pintype "power_in"))
      (node (ref "U2") (pin "G10") (pinfunction "VDD18TX0_G10") (pintype "power_in"))
      (node (ref "U2") (pin "H10") (pinfunction "VDD18TX1_H10") (pintype "power_in"))
      (node (ref "U2") (pin "J10") (pinfunction "VDD18RX1_J10") (pintype "power_in"))
      (node (ref "U2") (pin "J9") (pinfunction "VDD18RX1_J9") (pintype "power_in"))
    )
    (net (code "100") (name "/VDDCLK_1") (class "Default")
      (node (ref "C104") (pin "2") (pinfunction "2_2") (pintype "passive"))
      (node (ref "C105") (pin "2") (pinfunction "2_2") (pintype "passive"))
      (node (ref "L6") (pin "2") (pinfunction "2_2") (pintype "passive"))
      (node (ref "U2") (pin "G7") (pinfunction "VDDCLK_G7") (pintype "power_in"))
    )
    (net (code "101") (name "/XAUI_CLK0_N") (class "Default")
      (node (ref "C122") (pin "2") (pinfunction "2_2") (pintype "passive"))
    )
    (net (code "102") (name "/XAUI_CLK0_P") (class "Default")
      (node (ref "C81") (pin "2") (pinfunction "2_2") (pintype "passive"))
    )
    (net (code "103") (name "/XAUI_CLK1_N") (class "Default")
      (node (ref "C140") (pin "2") (pinfunction "2_2") (pintype "passive"))
      (node (ref "U2") (pin "F14") (pinfunction "XREFCKN_F14") (pintype "input"))
    )
    (net (code "104") (name "/XAUI_CLK1_P") (class "Default")
      (node (ref "C139") (pin "2") (pinfunction "2_2") (pintype "passive"))
      (node (ref "U2") (pin "F13") (pinfunction "XREFCKP_F13") (pintype "input"))
    )
    (net (code "105") (name "/XAUI_CLKAC0_N") (class "Default")
      (node (ref "C122") (pin "1") (pinfunction "1_1") (pintype "passive"))
      (node (ref "U6") (pin "16") (pinfunction "Q0n_16") (pintype "output"))
    )
    (net (code "106") (name "/XAUI_CLKAC0_P") (class "Default")
      (node (ref "C81") (pin "1") (pinfunction "1_1") (pintype "passive"))
      (node (ref "U6") (pin "15") (pinfunction "Q0_15") (pintype "output"))
    )
    (net (code "107") (name "/XAUI_CLKAC1_N") (class "Default")
      (node (ref "C140") (pin "1") (pinfunction "1_1") (pintype "passive"))
      (node (ref "U6") (pin "2") (pinfunction "Q1n_2") (pintype "output"))
    )
    (net (code "108") (name "/XAUI_CLKAC1_P") (class "Default")
      (node (ref "C139") (pin "1") (pinfunction "1_1") (pintype "passive"))
      (node (ref "U6") (pin "1") (pinfunction "Q1_1") (pintype "output"))
    )
    (net (code "109") (name "/XAUI_CLK_N") (class "Default")
      (node (ref "U6") (pin "12") (pinfunction "INn_12") (pintype "input"))
      (node (ref "U8") (pin "4") (pinfunction "OUT_4") (pintype "output"))
    )
    (net (code "110") (name "/XAUI_CLK_P") (class "Default")
      (node (ref "U6") (pin "9") (pinfunction "IN_9") (pintype "input"))
      (node (ref "U8") (pin "5") (pinfunction "COUT_5") (pintype "output"))
    )
    (net (code "111") (name "1V2_1") (class "Default")
      (node (ref "C100") (pin "2") (pinfunction "2_2") (pintype "passive"))
      (node (ref "C101") (pin "2") (pinfunction "2_2") (pintype "passive"))
      (node (ref "C102") (pin "2") (pinfunction "2_2") (pintype "passive"))
      (node (ref "C103") (pin "2") (pinfunction "2_2") (pintype "passive"))
      (node (ref "C58") (pin "2") (pinfunction "2_2") (pintype "passive"))
      (node (ref "L4") (pin "1") (pinfunction "1_1") (pintype "passive"))
      (node (ref "L6") (pin "1") (pinfunction "1_1") (pintype "passive"))
      (node (ref "U2") (pin "H4") (pinfunction "VDDB12_H4") (pintype "power_in"))
      (node (ref "U2") (pin "H5") (pinfunction "VDDB12_H5") (pintype "power_in"))
      (node (ref "U2") (pin "H7") (pinfunction "VDDB12_H7") (pintype "power_in"))
    )
    (net (code "112") (name "1V5") (class "Default")
      (node (ref "C91") (pin "2") (pinfunction "2_2") (pintype "passive"))
      (node (ref "U2") (pin "C7") (pinfunction "VDDMDIO_C7") (pintype "power_in"))
    )
    (net (code "113") (name "1V8") (class "Default")
      (node (ref "C94") (pin "2") (pinfunction "2_2") (pintype "passive"))
      (node (ref "L5") (pin "1") (pinfunction "1_1") (pintype "passive"))
    )
    (net (code "114") (name "2V5") (class "Default")
      (node (ref "C141") (pin "2") (pinfunction "2_2") (pintype "passive"))
      (node (ref "L11") (pin "1") (pinfunction "1_1") (pintype "passive"))
      (node (ref "U8") (pin "6") (pinfunction "VDD_6") (pintype "power_in"))
    )
    (net (code "115") (name "3V3") (class "Default")
      (node (ref "C92") (pin "2") (pinfunction "2_2") (pintype "passive"))
      (node (ref "C93") (pin "2") (pinfunction "2_2") (pintype "passive"))
      (node (ref "R57") (pin "2") (pinfunction "2_2") (pintype "passive"))
      (node (ref "R58") (pin "2") (pinfunction "2_2") (pintype "passive"))
      (node (ref "R59") (pin "2") (pinfunction "2_2") (pintype "passive"))
      (node (ref "R60") (pin "2") (pinfunction "2_2") (pintype "passive"))
      (node (ref "R61") (pin "2") (pinfunction "2_2") (pintype "passive"))
      (node (ref "R62") (pin "2") (pinfunction "2_2") (pintype "passive"))
      (node (ref "R63") (pin "2") (pinfunction "2_2") (pintype "passive"))
      (node (ref "U2") (pin "C9") (pinfunction "VDDTTLU_C9") (pintype "power_in"))
      (node (ref "U2") (pin "M6") (pinfunction "VDDTTLL_M6") (pintype "power_in"))
      (node (ref "U7") (pin "2") (pinfunction "A1_2") (pintype "input"))
      (node (ref "U7") (pin "3") (pinfunction "A2_3") (pintype "input"))
      (node (ref "U7") (pin "8") (pinfunction "VCC_8") (pintype "passive"))
    )
    (net (code "116") (name "<NO NET>") (class "Default")
      (node (ref "C103") (pin "1") (pinfunction "1_1") (pintype "passive"))
    )
    (net (code "117") (name "GND") (class "Default")
      (node (ref "C100") (pin "1") (pinfunction "1_1") (pintype "passive"))
      (node (ref "C101") (pin "1") (pinfunction "1_1") (pintype "passive"))
      (node (ref "C102") (pin "1") (pinfunction "1_1") (pintype "passive"))
      (node (ref "C104") (pin "1") (pinfunction "1_1") (pintype "passive"))
      (node (ref "C105") (pin "1") (pinfunction "1_1") (pintype "passive"))
      (node (ref "C106") (pin "1") (pinfunction "1_1") (pintype "passive"))
      (node (ref "C107") (pin "1") (pinfunction "1_1") (pintype "passive"))
      (node (ref "C108") (pin "1") (pinfunction "1_1") (pintype "passive"))
      (node (ref "C109") (pin "1") (pinfunction "1_1") (pintype "passive"))
      (node (ref "C112") (pin "2") (pinfunction "2_2") (pintype "passive"))
      (node (ref "C113") (pin "2") (pinfunction "2_2") (pintype "passive"))
      (node (ref "C115") (pin "2") (pinfunction "2_2") (pintype "passive"))
      (node (ref "C116") (pin "2") (pinfunction "2_2") (pintype "passive"))
      (node (ref "C117") (pin "2") (pinfunction "2_2") (pintype "passive"))
      (node (ref "C118") (pin "2") (pinfunction "2_2") (pintype "passive"))
      (node (ref "C119") (pin "2") (pinfunction "2_2") (pintype "passive"))
      (node (ref "C120") (pin "1") (pinfunction "1_1") (pintype "passive"))
      (node (ref "C121") (pin "1") (pinfunction "1_1") (pintype "passive"))
      (node (ref "C129") (pin "1") (pinfunction "1_1") (pintype "passive"))
      (node (ref "C130") (pin "1") (pinfunction "1_1") (pintype "passive"))
      (node (ref "C131") (pin "1") (pinfunction "1_1") (pintype "passive"))
      (node (ref "C141") (pin "1") (pinfunction "1_1") (pintype "passive"))
      (node (ref "C58") (pin "1") (pinfunction "1_1") (pintype "passive"))
      (node (ref "C61") (pin "1") (pinfunction "1_1") (pintype "passive"))
      (node (ref "C62") (pin "1") (pinfunction "1_1") (pintype "passive"))
      (node (ref "C86") (pin "1") (pinfunction "1_1") (pintype "passive"))
      (node (ref "C87") (pin "1") (pinfunction "1_1") (pintype "passive"))
      (node (ref "C88") (pin "1") (pinfunction "1_1") (pintype "passive"))
      (node (ref "C89") (pin "1") (pinfunction "1_1") (pintype "passive"))
      (node (ref "C90") (pin "1") (pinfunction "1_1") (pintype "passive"))
      (node (ref "C91") (pin "1") (pinfunction "1_1") (pintype "passive"))
      (node (ref "C92") (pin "1") (pinfunction "1_1") (pintype "passive"))
      (node (ref "C93") (pin "1") (pinfunction "1_1") (pintype "passive"))
      (node (ref "C94") (pin "1") (pinfunction "1_1") (pintype "passive"))
      (node (ref "C95") (pin "1") (pinfunction "1_1") (pintype "passive"))
      (node (ref "C96") (pin "1") (pinfunction "1_1") (pintype "passive"))
      (node (ref "C97") (pin "1") (pinfunction "1_1") (pintype "passive"))
      (node (ref "C98") (pin "1") (pinfunction "1_1") (pintype "passive"))
      (node (ref "C99") (pin "1") (pinfunction "1_1") (pintype "passive"))
      (node (ref "Q5") (pin "2") (pinfunction "S_2") (pintype "passive"))
      (node (ref "R40") (pin "1") (pinfunction "1_1") (pintype "passive"))
      (node (ref "R65") (pin "1") (pinfunction "1_1") (pintype "passive"))
      (node (ref "U2") (pin "A1") (pinfunction "GND_A1") (pintype "power_in"))
      (node (ref "U2") (pin "A11") (pinfunction "GND_A11") (pintype "power_in"))
      (node (ref "U2") (pin "A12") (pinfunction "GND_A12") (pintype "power_in"))
      (node (ref "U2") (pin "A13") (pinfunction "GND_A13") (pintype "power_in"))
      (node (ref "U2") (pin "A14") (pinfunction "GND_A14") (pintype "power_in"))
      (node (ref "U2") (pin "A2") (pinfunction "GND_A2") (pintype "power_in"))
      (node (ref "U2") (pin "A9") (pinfunction "GND_A9") (pintype "power_in"))
      (node (ref "U2") (pin "B1") (pinfunction "GND_B1") (pintype "power_in"))
      (node (ref "U2") (pin "B11") (pinfunction "GND_B11") (pintype "power_in"))
      (node (ref "U2") (pin "B12") (pinfunction "GND_B12") (pintype "power_in"))
      (node (ref "U2") (pin "B2") (pinfunction "GND_B2") (pintype "power_in"))
      (node (ref "U2") (pin "B9") (pinfunction "GND_B9") (pintype "power_in"))
      (node (ref "U2") (pin "C12") (pinfunction "GND_C12") (pintype "power_in"))
      (node (ref "U2") (pin "C13") (pinfunction "GND_C13") (pintype "power_in"))
      (node (ref "U2") (pin "C14") (pinfunction "GND_C14") (pintype "power_in"))
      (node (ref "U2") (pin "C4") (pinfunction "GND_C4") (pintype "power_in"))
      (node (ref "U2") (pin "C5") (pinfunction "GND_C5") (pintype "power_in"))
      (node (ref "U2") (pin "D12") (pinfunction "GND_D12") (pintype "power_in"))
      (node (ref "U2") (pin "D3") (pinfunction "GND_D3") (pintype "power_in"))
      (node (ref "U2") (pin "E12") (pinfunction "GND_E12") (pintype "power_in"))
      (node (ref "U2") (pin "E13") (pinfunction "GND_E13") (pintype "power_in"))
      (node (ref "U2") (pin "E14") (pinfunction "GND_E14") (pintype "power_in"))
      (node (ref "U2") (pin "E3") (pinfunction "GND_E3") (pintype "power_in"))
      (node (ref "U2") (pin "F11") (pinfunction "GND_F11") (pintype "power_in"))
      (node (ref "U2") (pin "F12") (pinfunction "GND_F12") (pintype "power_in"))
      (node (ref "U2") (pin "F3") (pinfunction "GND_F3") (pintype "power_in"))
      (node (ref "U2") (pin "F6") (pinfunction "GND_F6") (pintype "power_in"))
      (node (ref "U2") (pin "F8") (pinfunction "GND_F8") (pintype "power_in"))
      (node (ref "U2") (pin "G1") (pinfunction "GND_G1") (pintype "power_in"))
      (node (ref "U2") (pin "G11") (pinfunction "GND_G11") (pintype "power_in"))
      (node (ref "U2") (pin "G12") (pinfunction "GND_G12") (pintype "power_in"))
      (node (ref "U2") (pin "G13") (pinfunction "GND_G13") (pintype "power_in"))
      (node (ref "U2") (pin "G14") (pinfunction "GND_G14") (pintype "power_in"))
      (node (ref "U2") (pin "G2") (pinfunction "GND_G2") (pintype "power_in"))
      (node (ref "U2") (pin "G3") (pinfunction "GND_G3") (pintype "power_in"))
      (node (ref "U2") (pin "G6") (pinfunction "GND_G6") (pintype "power_in"))
      (node (ref "U2") (pin "G8") (pinfunction "GND_G8") (pintype "power_in"))
      (node (ref "U2") (pin "H11") (pinfunction "GND_H11") (pintype "power_in"))
      (node (ref "U2") (pin "H13") (pinfunction "GND_H13") (pintype "power_in"))
      (node (ref "U2") (pin "H3") (pinfunction "GND_H3") (pintype "power_in"))
      (node (ref "U2") (pin "H6") (pinfunction "GND_H6") (pintype "power_in"))
      (node (ref "U2") (pin "H8") (pinfunction "GND_H8") (pintype "power_in"))
      (node (ref "U2") (pin "J11") (pinfunction "GND_J11") (pintype "power_in"))
      (node (ref "U2") (pin "J13") (pinfunction "GND_J13") (pintype "power_in"))
      (node (ref "U2") (pin "J3") (pinfunction "GND_J3") (pintype "power_in"))
      (node (ref "U2") (pin "J6") (pinfunction "GND_J6") (pintype "power_in"))
      (node (ref "U2") (pin "J8") (pinfunction "GND_J8") (pintype "power_in"))
      (node (ref "U2") (pin "K12") (pinfunction "GND_K12") (pintype "power_in"))
      (node (ref "U2") (pin "K13") (pinfunction "GND_K13") (pintype "power_in"))
      (node (ref "U2") (pin "K14") (pinfunction "GND_K14") (pintype "power_in"))
      (node (ref "U2") (pin "K3") (pinfunction "GND_K3") (pintype "power_in"))
      (node (ref "U2") (pin "L12") (pinfunction "GND_L12") (pintype "power_in"))
      (node (ref "U2") (pin "L3") (pinfunction "GND_L3") (pintype "power_in"))
      (node (ref "U2") (pin "L9") (pinfunction "SCAN_EN_L9") (pintype "input"))
      (node (ref "U2") (pin "M1") (pinfunction "GND_M1") (pintype "power_in"))
      (node (ref "U2") (pin "M12") (pinfunction "GND_M12") (pintype "power_in"))
      (node (ref "U2") (pin "M13") (pinfunction "GND_M13") (pintype "power_in"))
      (node (ref "U2") (pin "M14") (pinfunction "GND_M14") (pintype "power_in"))
      (node (ref "U2") (pin "M2") (pinfunction "GND_M2") (pintype "power_in"))
      (node (ref "U2") (pin "M4") (pinfunction "GND_M4") (pintype "power_in"))
      (node (ref "U2") (pin "N1") (pinfunction "GND_N1") (pintype "power_in"))
      (node (ref "U2") (pin "N10") (pinfunction "GND_N10") (pintype "power_in"))
      (node (ref "U2") (pin "N12") (pinfunction "GND_N12") (pintype "power_in"))
      (node (ref "U2") (pin "N6") (pinfunction "GND_N6") (pintype "power_in"))
      (node (ref "U2") (pin "N8") (pinfunction "GND_N8") (pintype "power_in"))
      (node (ref "U2") (pin "P1") (pinfunction "GND_P1") (pintype "power_in"))
      (node (ref "U2") (pin "P10") (pinfunction "GND_P10") (pintype "power_in"))
      (node (ref "U2") (pin "P12") (pinfunction "GND_P12") (pintype "power_in"))
      (node (ref "U2") (pin "P13") (pinfunction "GND_P13") (pintype "power_in"))
      (node (ref "U2") (pin "P14") (pinfunction "GND_P14") (pintype "power_in"))
      (node (ref "U2") (pin "P6") (pinfunction "GND_P6") (pintype "power_in"))
      (node (ref "U2") (pin "P8") (pinfunction "GND_P8") (pintype "power_in"))
      (node (ref "U6") (pin "13") (pinfunction "GND_13") (pintype "power_in"))
      (node (ref "U6") (pin "17") (pinfunction "GND_17") (pintype "power_in"))
      (node (ref "U7") (pin "4") (pinfunction "GND_4") (pintype "passive"))
      (node (ref "U8") (pin "3") (pinfunction "GND_3") (pintype "power_in"))
    )
    (net (code "118") (name "Net-(C106-Pad2)") (class "Default")
      (node (ref "C106") (pin "2") (pinfunction "2_2") (pintype "passive"))
      (node (ref "C107") (pin "2") (pinfunction "2_2") (pintype "passive"))
      (node (ref "C108") (pin "2") (pinfunction "2_2") (pintype "passive"))
      (node (ref "C109") (pin "2") (pinfunction "2_2") (pintype "passive"))
      (node (ref "L11") (pin "2") (pinfunction "2_2") (pintype "passive"))
      (node (ref "U6") (pin "14") (pinfunction "VCC_14") (pintype "power_in"))
      (node (ref "U6") (pin "7") (pinfunction "VCC_7") (pintype "power_in"))
    )
    (net (code "119") (name "Net-(Q5-D)") (class "Default")
      (node (ref "Q5") (pin "3") (pinfunction "D_3") (pintype "passive"))
      (node (ref "U2") (pin "C6") (pinfunction "RESETN_C6") (pintype "input"))
    )
    (net (code "120") (name "Net-(U2B-CMUFILT0)") (class "Default")
      (node (ref "C116") (pin "1") (pinfunction "1_1") (pintype "passive"))
      (node (ref "U2") (pin "E11") (pinfunction "CMUFILT0_E11") (pintype "passive"))
    )
    (net (code "121") (name "Net-(U2B-CMUFILT1)") (class "Default")
      (node (ref "C117") (pin "1") (pinfunction "1_1") (pintype "passive"))
      (node (ref "U2") (pin "P11") (pinfunction "CMUFILT1_P11") (pintype "passive"))
    )
    (net (code "122") (name "Net-(U2B-CMUFILTER)") (class "Default")
      (node (ref "C115") (pin "1") (pinfunction "1_1") (pintype "passive"))
      (node (ref "U2") (pin "L11") (pinfunction "CMUFILTER_L11") (pintype "passive"))
    )
    (net (code "123") (name "Net-(U2B-RXCRUFILT0)") (class "Default")
      (node (ref "C118") (pin "1") (pinfunction "1_1") (pintype "passive"))
      (node (ref "U2") (pin "C11") (pinfunction "RXCRUFILT0_C11") (pintype "passive"))
    )
    (net (code "124") (name "Net-(U2B-RXCRUFILT1)") (class "Default")
      (node (ref "C119") (pin "1") (pinfunction "1_1") (pintype "passive"))
      (node (ref "U2") (pin "M11") (pinfunction "RXCRUFILT1_M11") (pintype "passive"))
    )
    (net (code "125") (name "Net-(U2B-RXINCM0)") (class "Default")
      (node (ref "C120") (pin "2") (pinfunction "2_2") (pintype "passive"))
      (node (ref "U2") (pin "D11") (pinfunction "RXINCM0_D11") (pintype "passive"))
    )
    (net (code "126") (name "Net-(U2B-RXINCM1)") (class "Default")
      (node (ref "C121") (pin "2") (pinfunction "2_2") (pintype "passive"))
      (node (ref "U2") (pin "N11") (pinfunction "RXINCM1_N11") (pintype "passive"))
    )
    (net (code "127") (name "Net-(U2C-XAUIFILT0)") (class "Default")
      (node (ref "C113") (pin "1") (pinfunction "1_1") (pintype "passive"))
      (node (ref "U2") (pin "C3") (pinfunction "XAUIFILT0_C3") (pintype "passive"))
    )
    (net (code "128") (name "Net-(U2C-XAUIFILT1)") (class "Default")
      (node (ref "C112") (pin "1") (pinfunction "1_1") (pintype "passive"))
      (node (ref "U2") (pin "M3") (pinfunction "XAUIFILT1_M3") (pintype "passive"))
    )
    (net (code "129") (name "Net-(U2D-PADDR1)") (class "Default")
      (node (ref "R60") (pin "1") (pinfunction "1_1") (pintype "passive"))
      (node (ref "U2") (pin "D10") (pinfunction "PADDR1_D10") (pintype "input"))
    )
    (net (code "130") (name "Net-(U2D-PADDR2)") (class "Default")
      (node (ref "R61") (pin "1") (pinfunction "1_1") (pintype "passive"))
      (node (ref "U2") (pin "C8") (pinfunction "PADDR2_C8") (pintype "input"))
    )
    (net (code "131") (name "Net-(U2D-PADDR3)") (class "Default")
      (node (ref "R62") (pin "1") (pinfunction "1_1") (pintype "passive"))
      (node (ref "U2") (pin "E10") (pinfunction "PADDR3_E10") (pintype "input"))
    )
    (net (code "132") (name "Net-(U2D-PADDR4)") (class "Default")
      (node (ref "R63") (pin "1") (pinfunction "1_1") (pintype "passive"))
      (node (ref "U2") (pin "E6") (pinfunction "PADDR4_E6") (pintype "input"))
    )
    (net (code "133") (name "Net-(U2D-STWA0)") (class "Default")
      (node (ref "R57") (pin "1") (pinfunction "1_1") (pintype "passive"))
      (node (ref "U2") (pin "B7") (pinfunction "STWA0_B7") (pintype "input"))
    )
    (net (code "134") (name "Net-(U2D-STWA1)") (class "Default")
      (node (ref "R58") (pin "1") (pinfunction "1_1") (pintype "passive"))
      (node (ref "U2") (pin "A7") (pinfunction "STWA1_A7") (pintype "input"))
    )
    (net (code "135") (name "Net-(U2D-STWA2)") (class "Default")
      (node (ref "R59") (pin "1") (pinfunction "1_1") (pintype "passive"))
      (node (ref "U2") (pin "C10") (pinfunction "STWA2_C10") (pintype "input"))
    )
    (net (code "136") (name "Net-(U2D-TMON)") (class "Default")
      (node (ref "TP20") (pin "1") (pinfunction "1_1") (pintype "passive"))
      (node (ref "U2") (pin "M10") (pinfunction "TMON_M10") (pintype "passive"))
    )
    (net (code "137") (name "Net-(U6-EN)") (class "Default")
      (node (ref "R65") (pin "2") (pinfunction "2_2") (pintype "passive"))
      (node (ref "U6") (pin "8") (pinfunction "EN_8") (pintype "input"))
      (node (ref "U8") (pin "1") (pinfunction "E/D_1") (pintype "input"))
    )
    (net (code "138") (name "Net-(U6-Q2)") (class "Default")
      (node (ref "R69") (pin "2") (pinfunction "2_2") (pintype "passive"))
      (node (ref "U6") (pin "3") (pinfunction "Q2_3") (pintype "output"))
    )
    (net (code "139") (name "Net-(U6-Q2n)") (class "Default")
      (node (ref "R69") (pin "1") (pinfunction "1_1") (pintype "passive"))
      (node (ref "U6") (pin "4") (pinfunction "Q2n_4") (pintype "output"))
    )
    (net (code "140") (name "Net-(U6-Q3)") (class "Default")
      (node (ref "R64") (pin "2") (pinfunction "2_2") (pintype "passive"))
      (node (ref "U6") (pin "5") (pinfunction "Q3_5") (pintype "output"))
    )
    (net (code "141") (name "Net-(U6-Q3n)") (class "Default")
      (node (ref "R64") (pin "1") (pinfunction "1_1") (pintype "passive"))
      (node (ref "U6") (pin "6") (pinfunction "Q3n_6") (pintype "output"))
    )
    (net (code "142") (name "Net-(U7-WP)") (class "Default")
      (node (ref "R40") (pin "2") (pinfunction "2_2") (pintype "passive"))
      (node (ref "U7") (pin "7") (pinfunction "WP_7") (pintype "input"))
    )
    (net (code "143") (name "unconnected-(U2B-RX0CKOUTN-PadA8)") (class "Default")
      (node (ref "U2") (pin "A8") (pinfunction "RX0CKOUTN_A8") (pintype "output+no_connect"))
    )
    (net (code "144") (name "unconnected-(U2B-RX0CKOUTP-PadB8)") (class "Default")
      (node (ref "U2") (pin "B8") (pinfunction "RX0CKOUTP_B8") (pintype "output+no_connect"))
    )
    (net (code "145") (name "unconnected-(U2B-RX1CKOUTN-PadP7)") (class "Default")
      (node (ref "U2") (pin "P7") (pinfunction "RX1CKOUTN_P7") (pintype "output+no_connect"))
    )
    (net (code "146") (name "unconnected-(U2B-RX1CKOUTP-PadN7)") (class "Default")
      (node (ref "U2") (pin "N7") (pinfunction "RX1CKOUTP_N7") (pintype "output+no_connect"))
    )
    (net (code "147") (name "unconnected-(U2B-SREFCKN-PadJ12)") (class "Default")
      (node (ref "U2") (pin "J12") (pinfunction "SREFCKN_J12") (pintype "input+no_connect"))
    )
    (net (code "148") (name "unconnected-(U2B-SREFCKP-PadH12)") (class "Default")
      (node (ref "U2") (pin "H12") (pinfunction "SREFCKP_H12") (pintype "input+no_connect"))
    )
    (net (code "149") (name "unconnected-(U2B-TX0CKOUTN-PadA10)") (class "Default")
      (node (ref "U2") (pin "A10") (pinfunction "TX0CKOUTN_A10") (pintype "output+no_connect"))
    )
    (net (code "150") (name "unconnected-(U2B-TX0CKOUTP-PadB10)") (class "Default")
      (node (ref "U2") (pin "B10") (pinfunction "TX0CKOUTP_B10") (pintype "output+no_connect"))
    )
    (net (code "151") (name "unconnected-(U2B-TX1CKOUTN-PadP9)") (class "Default")
      (node (ref "U2") (pin "P9") (pinfunction "TX1CKOUTN_P9") (pintype "output+no_connect"))
    )
    (net (code "152") (name "unconnected-(U2B-TX1CKOUTP-PadN9)") (class "Default")
      (node (ref "U2") (pin "N9") (pinfunction "TX1CKOUTP_N9") (pintype "output+no_connect"))
    )
    (net (code "153") (name "unconnected-(U2B-WREFCKN-PadJ14)") (class "Default")
      (node (ref "U2") (pin "J14") (pinfunction "WREFCKN_J14") (pintype "input+no_connect"))
    )
    (net (code "154") (name "unconnected-(U2B-WREFCKP-PadH14)") (class "Default")
      (node (ref "U2") (pin "H14") (pinfunction "WREFCKP_H14") (pintype "input+no_connect"))
    )
    (net (code "155") (name "unconnected-(U2D-ANATEST-PadM8)") (class "Default")
      (node (ref "U2") (pin "M8") (pinfunction "ANATEST_M8") (pintype "passive+no_connect"))
    )
    (net (code "156") (name "unconnected-(U2D-RSVD1-PadD8)") (class "Default")
      (node (ref "U2") (pin "D8") (pinfunction "RSVD1_D8") (pintype "passive+no_connect"))
    )
    (net (code "157") (name "unconnected-(U2D-RSVD2-PadE8)") (class "Default")
      (node (ref "U2") (pin "E8") (pinfunction "RSVD2_E8") (pintype "passive+no_connect"))
    )
    (net (code "158") (name "unconnected-(U2D-RSVD3-PadK7)") (class "Default")
      (node (ref "U2") (pin "K7") (pinfunction "RSVD3_K7") (pintype "passive+no_connect"))
    )
    (net (code "159") (name "unconnected-(U2D-RSVD4-PadL7)") (class "Default")
      (node (ref "U2") (pin "L7") (pinfunction "RSVD4_L7") (pintype "passive+no_connect"))
    )
    (net (code "160") (name "unconnected-(U2D-TCK-PadK9)") (class "Default")
      (node (ref "U2") (pin "K9") (pinfunction "TCK_K9") (pintype "input+no_connect"))
    )
    (net (code "161") (name "unconnected-(U2D-TDI-PadL8)") (class "Default")
      (node (ref "U2") (pin "L8") (pinfunction "TDI_L8") (pintype "input+no_connect"))
    )
    (net (code "162") (name "unconnected-(U2D-TDO-PadK8)") (class "Default")
      (node (ref "U2") (pin "K8") (pinfunction "TDO_K8") (pintype "output+no_connect"))
    )
    (net (code "163") (name "unconnected-(U2D-TMS-PadM5)") (class "Default")
      (node (ref "U2") (pin "M5") (pinfunction "TMS_M5") (pintype "input+no_connect"))
    )
    (net (code "164") (name "unconnected-(U6-VREF-AC-Pad10)") (class "Default")
      (node (ref "U6") (pin "10") (pinfunction "VREF-AC_10") (pintype "power_in+no_connect"))
    )
    (net (code "165") (name "unconnected-(U6-VT-Pad11)") (class "Default")
      (node (ref "U6") (pin "11") (pinfunction "VT_11") (pintype "power_in+no_connect"))
    )
    (net (code "166") (name "unconnected-(U7-NC-Pad1)") (class "Default")
      (node (ref "U7") (pin "1") (pinfunction "NC_1") (pintype "passive+no_connect"))
    )
    (net (code "167") (name "unconnected-(U8-NC-Pad2)") (class "Default")
      (node (ref "U8") (pin "2") (pinfunction "NC_2") (pintype "passive+no_connect"))
    )
  )
)
